# SW6124_A_A_B_C_MCU_LED.net
KiCad netlist of a schematic drawn in Altium Designer
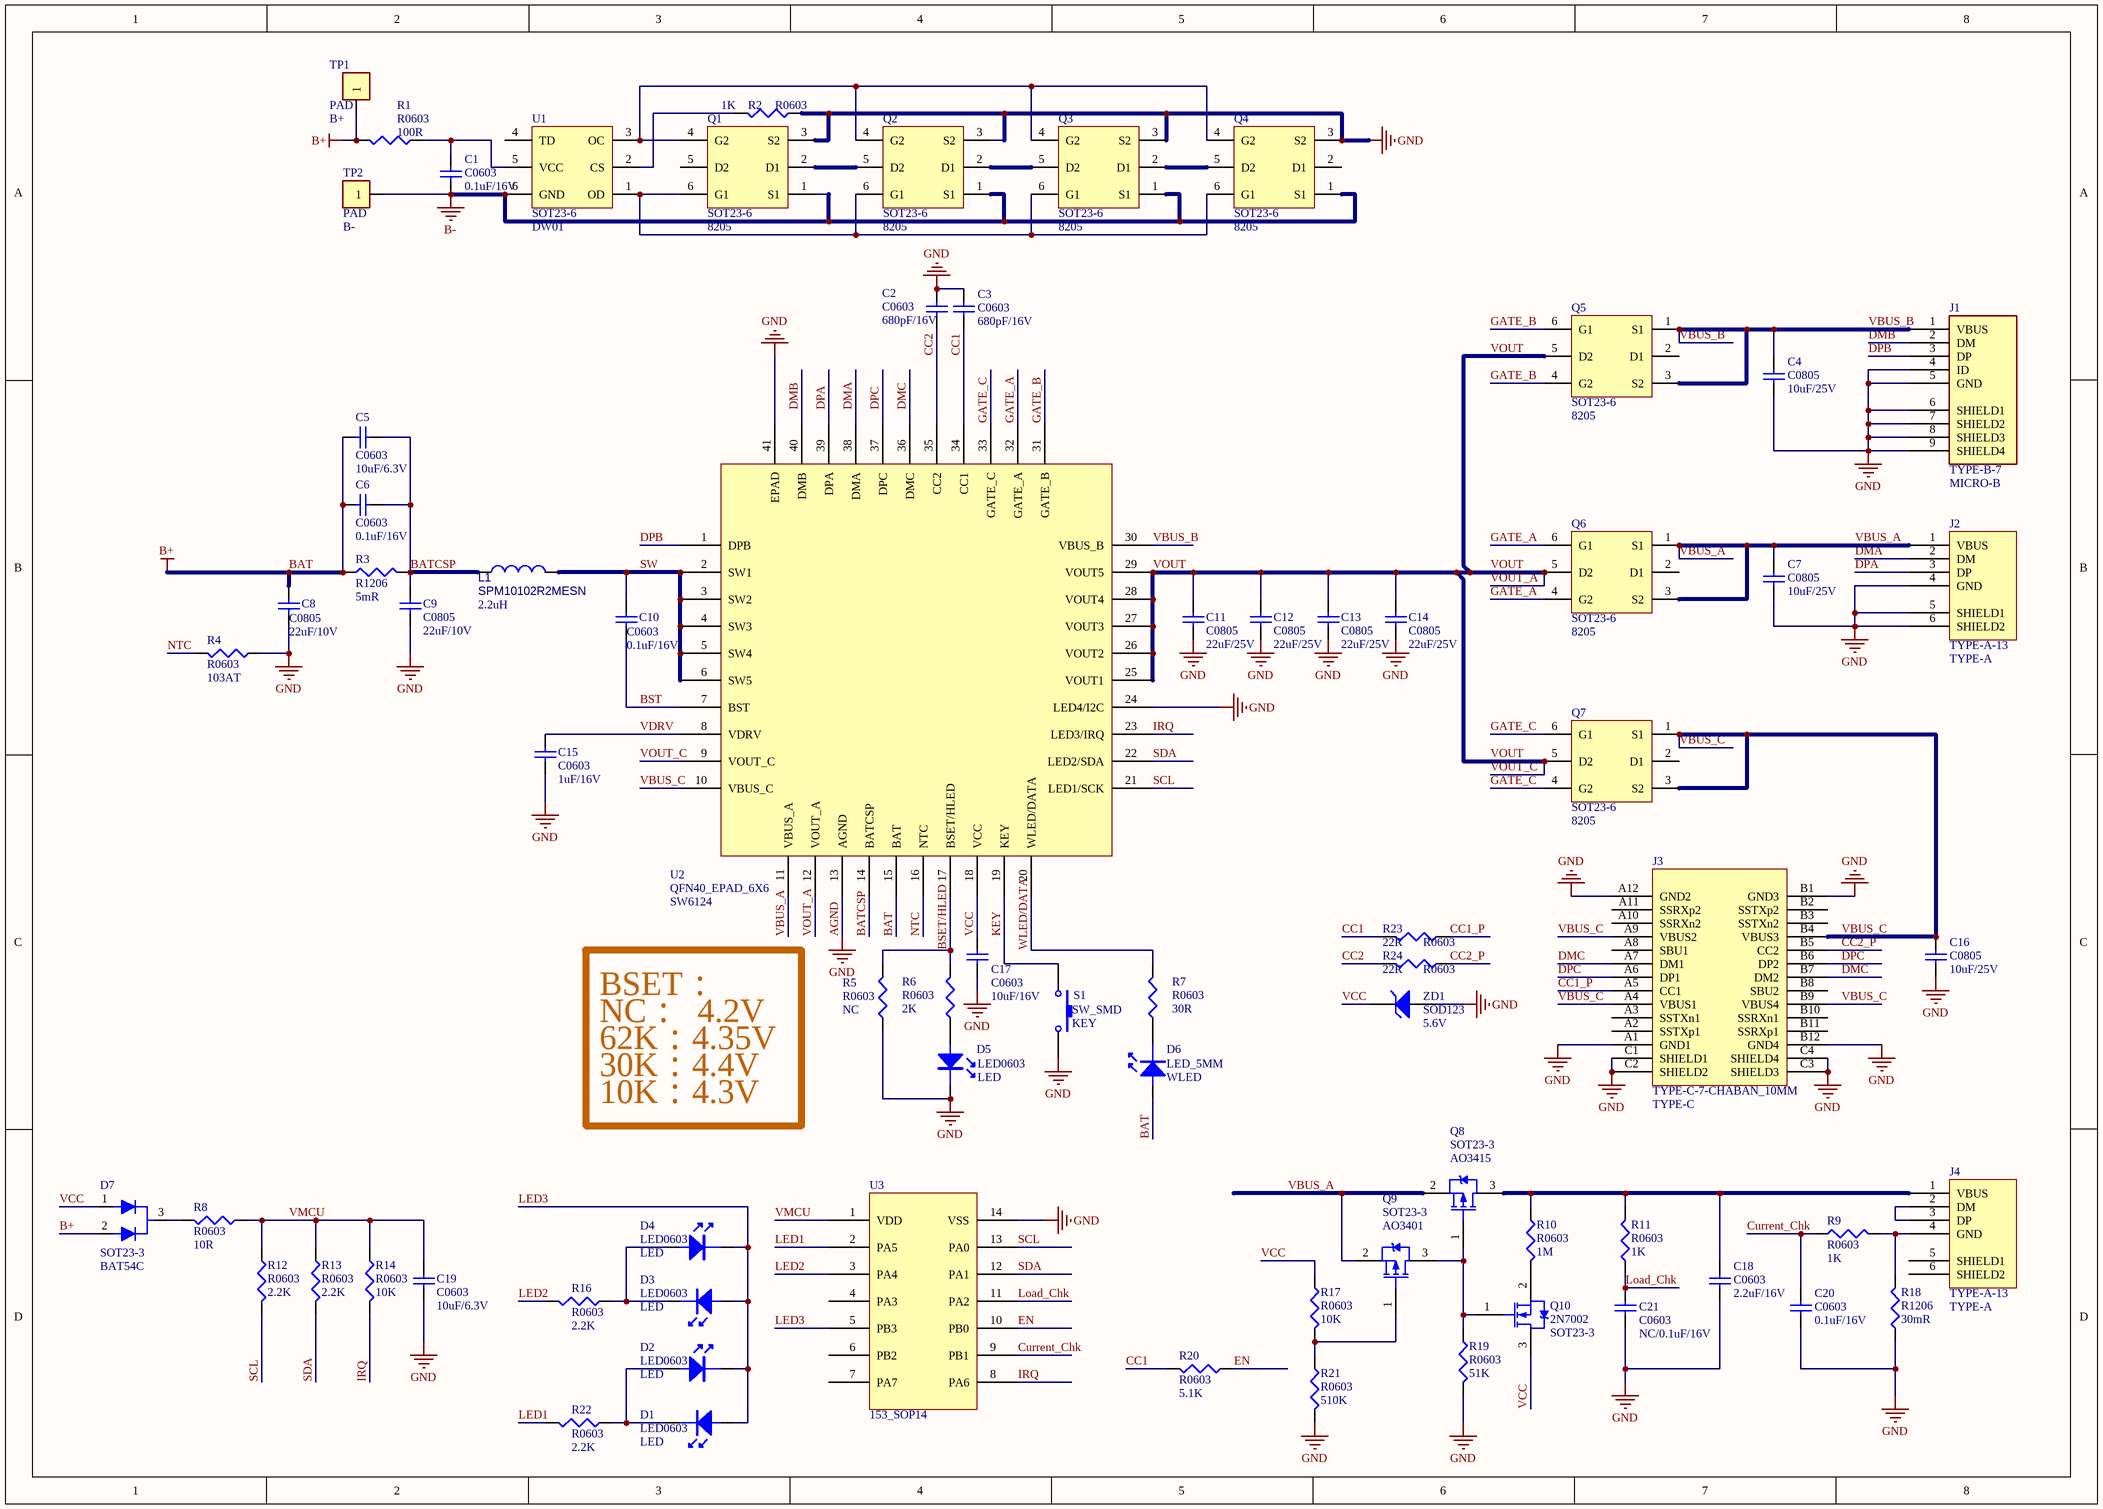
[diagram p0: SW6124+A+A+B+C+MCU+LED.SchDoc]

(export (version "E")
  (design (tool "Eeschema 10.0.6"))
  (components
    (comp (ref "C1")
      (value "C0603")
      (footprint "C0603")
      (description "Capacitor")
      (fields (field (name "ALTIUM_VALUE") "0.1uF/16V") (field (name "PUBLISHER") "Altium Limited"))
      (libsource (lib "*") (part "Cap"))
    )
    (comp (ref "C2")
      (value "C0603")
      (footprint "C0603")
      (description "Capacitor")
      (fields (field (name "ALTIUM_VALUE") "680pF/16V") (field (name "PUBLISHER") "Altium Limited"))
      (libsource (lib "*") (part "CAP0603"))
    )
    (comp (ref "C3")
      (value "C0603")
      (footprint "C0603")
      (description "Capacitor")
      (fields (field (name "ALTIUM_VALUE") "680pF/16V") (field (name "PUBLISHER") "Altium Limited"))
      (libsource (lib "*") (part "CAP0603"))
    )
    (comp (ref "C4")
      (value "C0805")
      (footprint "C0805")
      (description "Capacitor")
      (fields (field (name "ALTIUM_VALUE") "10uF/25V") (field (name "PUBLISHER") "Altium Limited"))
      (libsource (lib "*") (part "CAP0603"))
    )
    (comp (ref "C5")
      (value "C0603")
      (footprint "C0603")
      (description "Capacitor")
      (fields (field (name "ALTIUM_VALUE") "10uF/6.3V") (field (name "PUBLISHER") "Altium Limited"))
      (libsource (lib "*") (part "CAP0603"))
    )
    (comp (ref "C6")
      (value "C0603")
      (footprint "C0603")
      (description "Capacitor")
      (fields (field (name "ALTIUM_VALUE") "0.1uF/16V") (field (name "PUBLISHER") "Altium Limited"))
      (libsource (lib "*") (part "CAP0603"))
    )
    (comp (ref "C7")
      (value "C0805")
      (footprint "C0805")
      (description "Capacitor")
      (fields (field (name "ALTIUM_VALUE") "10uF/25V") (field (name "PUBLISHER") "Altium Limited"))
      (libsource (lib "*") (part "CAP0603"))
    )
    (comp (ref "C8")
      (value "C0805")
      (footprint "C0805")
      (description "Capacitor")
      (fields (field (name "ALTIUM_VALUE") "22uF/10V") (field (name "PUBLISHER") "Altium Limited"))
      (libsource (lib "*") (part "CAP0805"))
    )
    (comp (ref "C9")
      (value "C0805")
      (footprint "C0805")
      (description "Capacitor")
      (fields (field (name "ALTIUM_VALUE") "22uF/10V") (field (name "PUBLISHER") "Altium Limited"))
      (libsource (lib "*") (part "CAP0805"))
    )
    (comp (ref "C10")
      (value "C0603")
      (footprint "C0603")
      (description "Capacitor")
      (fields (field (name "ALTIUM_VALUE") "0.1uF/16V") (field (name "PUBLISHER") "Altium Limited"))
      (libsource (lib "*") (part "CAP0603"))
    )
    (comp (ref "C11")
      (value "C0805")
      (footprint "C0805")
      (description "Capacitor")
      (fields (field (name "ALTIUM_VALUE") "22uF/25V") (field (name "PUBLISHER") "Altium Limited"))
      (libsource (lib "*") (part "CAP0805"))
    )
    (comp (ref "C12")
      (value "C0805")
      (footprint "C0805")
      (description "Capacitor")
      (fields (field (name "ALTIUM_VALUE") "22uF/25V") (field (name "PUBLISHER") "Altium Limited"))
      (libsource (lib "*") (part "CAP0805"))
    )
    (comp (ref "C13")
      (value "C0805")
      (footprint "C0805")
      (description "Capacitor")
      (fields (field (name "ALTIUM_VALUE") "22uF/25V") (field (name "PUBLISHER") "Altium Limited"))
      (libsource (lib "*") (part "CAP0805"))
    )
    (comp (ref "C14")
      (value "C0805")
      (footprint "C0805")
      (description "Capacitor")
      (fields (field (name "ALTIUM_VALUE") "22uF/25V") (field (name "PUBLISHER") "Altium Limited"))
      (libsource (lib "*") (part "CAP0805"))
    )
    (comp (ref "C15")
      (value "C0603")
      (footprint "C0603")
      (description "Capacitor")
      (fields (field (name "ALTIUM_VALUE") "1uF/16V") (field (name "PUBLISHER") "Altium Limited"))
      (libsource (lib "*") (part "CAP0603"))
    )
    (comp (ref "C16")
      (value "C0805")
      (footprint "C0805")
      (description "Capacitor")
      (fields (field (name "ALTIUM_VALUE") "10uF/25V") (field (name "PUBLISHER") "Altium Limited"))
      (libsource (lib "*") (part "CAP0603"))
    )
    (comp (ref "C17")
      (value "C0603")
      (footprint "C0603")
      (description "Capacitor")
      (fields (field (name "ALTIUM_VALUE") "10uF/16V") (field (name "PUBLISHER") "Altium Limited"))
      (libsource (lib "*") (part "CAP0603"))
    )
    (comp (ref "C18")
      (value "C0603")
      (footprint "C0603")
      (description "Capacitor")
      (fields (field (name "ALTIUM_VALUE") "2.2uF/16V") (field (name "PUBLISHER") "Altium Limited"))
      (libsource (lib "*") (part "CAP0603"))
    )
    (comp (ref "C19")
      (value "C0603")
      (footprint "C0603")
      (description "Capacitor")
      (fields (field (name "ALTIUM_VALUE") "10uF/6.3V") (field (name "PUBLISHER") "Altium Limited"))
      (libsource (lib "*") (part "CAP0603"))
    )
    (comp (ref "C20")
      (value "C0603")
      (footprint "C0603")
      (description "Capacitor")
      (fields (field (name "ALTIUM_VALUE") "0.1uF/16V") (field (name "PUBLISHER") "Altium Limited"))
      (libsource (lib "*") (part "CAP0603"))
    )
    (comp (ref "C21")
      (value "C0603")
      (footprint "C0603")
      (description "Capacitor")
      (fields (field (name "ALTIUM_VALUE") "NC/0.1uF/16V") (field (name "PUBLISHER") "Altium Limited"))
      (libsource (lib "*") (part "CAP0603"))
    )
    (comp (ref "D1") (value "LED") (footprint "LED0603") (libsource (lib "*") (part "LED")))
    (comp (ref "D2") (value "LED") (footprint "LED0603") (libsource (lib "*") (part "LED")))
    (comp (ref "D3") (value "LED") (footprint "LED0603") (libsource (lib "*") (part "LED")))
    (comp (ref "D4") (value "LED") (footprint "LED0603") (libsource (lib "*") (part "LED")))
    (comp (ref "D5") (value "LED") (footprint "LED0603") (libsource (lib "*") (part "LED")))
    (comp (ref "D6")
      (value "WLED")
      (footprint "LED_5MM")
      (fields (field (name "FOOTPRINF") "LED_5MM") (field (name "Comment") "LED_5MM"))
      (libsource (lib "*") (part "LED"))
    )
    (comp (ref "D7") (value "BAT54C") (footprint "SOT23-3") (libsource (lib "Schlib1-2012") (part "D3")))
    (comp (ref "J1")
      (value "MICRO-B")
      (footprint "TYPE-B-7")
      (fields (field (name "FOOTPRINTF") "TYPE-B-7") (field (name "Comment") "USB_MICRO_B"))
      (libsource (lib "*") (part "USB_MICRO_B"))
    )
    (comp (ref "J2")
      (value "TYPE-A")
      (footprint "TYPE-A-13")
      (fields (field (name "FOOTPRINF") "TYPE-A-13") (field (name "Comment") "TYPE-A-1"))
      (libsource (lib "*") (part "TYPE-A-1"))
    )
    (comp (ref "J3")
      (value "TYPE-C")
      (footprint "TYPE-C-7-CHABAN_10MM")
      (libsource (lib "*") (part "TYPE-C"))
    )
    (comp (ref "J4")
      (value "TYPE-A")
      (footprint "PIE10-USB")
      (fields (field (name "FOOTPRINF") "TYPE-A-13") (field (name "Comment") "TYPE-A-1"))
      (libsource (lib "*") (part "TYPE-A-1"))
    )
    (comp (ref "L1")
      (value "SPM10102R2MESN")
      (footprint "INDUCTOR_SPM1010")
      (fields (field (name "ALTIUM_VALUE") "2.2uH"))
      (libsource (lib "*") (part "INDUCTOR"))
    )
    (comp (ref "Q1")
      (value "8205")
      (footprint "SOT23-6")
      (fields (field (name "FOOTPRINF") "SOT23-6"))
      (libsource (lib "*") (part "8205B"))
    )
    (comp (ref "Q2")
      (value "8205")
      (footprint "SOT23-6")
      (fields (field (name "FOOTPRINF") "SOT23-6"))
      (libsource (lib "*") (part "8205B"))
    )
    (comp (ref "Q3")
      (value "8205")
      (footprint "SOT23-6")
      (fields (field (name "FOOTPRINF") "SOT23-6"))
      (libsource (lib "*") (part "8205B"))
    )
    (comp (ref "Q4")
      (value "8205")
      (footprint "SOT23-6")
      (fields (field (name "FOOTPRINF") "SOT23-6"))
      (libsource (lib "*") (part "8205B"))
    )
    (comp (ref "Q5")
      (value "8205")
      (footprint "SOT23-6")
      (fields (field (name "FOOTPRINF") "SOT23-6"))
      (libsource (lib "") (part "8205B_1"))
    )
    (comp (ref "Q6")
      (value "8205")
      (footprint "SOT23-6")
      (fields (field (name "FOOTPRINF") "SOT23-6"))
      (libsource (lib "") (part "8205B_1"))
    )
    (comp (ref "Q7")
      (value "8205")
      (footprint "SOT23-6")
      (fields (field (name "FOOTPRINF") "SOT23-6"))
      (libsource (lib "") (part "8205B_1"))
    )
    (comp (ref "Q8")
      (value "AO3415")
      (footprint "SOT23-3")
      (description "P-Channel Power MOSFET")
      (fields (field (name "Comment") "PMOS-2") (field (name "PUBLISHER") "Altium Limited"))
      (libsource (lib "Miscellaneous Devices") (part "PMOS-2"))
    )
    (comp (ref "Q9")
      (value "AO3401")
      (footprint "SOT23-3")
      (description "P-Channel Power MOSFET")
      (fields (field (name "Comment") "PMOS-2") (field (name "PUBLISHER") "Altium Limited"))
      (libsource (lib "Miscellaneous Devices") (part "PMOS-2"))
    )
    (comp (ref "Q10")
      (value "2N7002")
      (footprint "SOT23-3")
      (description "N-Channel Power MOSFET")
      (fields (field (name "Comment") "NMOS-2") (field (name "PUBLISHER") "Altium Limited"))
      (libsource (lib "Miscellaneous Devices") (part "NMOS-2"))
    )
    (comp (ref "R1")
      (value "R0603")
      (footprint "R0603")
      (description "Resistor")
      (fields (field (name "ALTIUM_VALUE") "100R") (field (name "PUBLISHER") "Altium Limited"))
      (libsource (lib "*") (part "Res3"))
    )
    (comp (ref "R2")
      (value "R0603")
      (footprint "R0603")
      (description "Resistor")
      (fields (field (name "ALTIUM_VALUE") "1K") (field (name "PUBLISHER") "Altium Limited"))
      (libsource (lib "*") (part "Res3"))
    )
    (comp (ref "R3")
      (value "R1206")
      (footprint "R1206")
      (description "Resistor")
      (fields (field (name "ALTIUM_VALUE") "5mR") (field (name "PUBLISHER") "Altium Limited"))
      (libsource (lib "*") (part "RES"))
    )
    (comp (ref "R4")
      (value "R0603")
      (footprint "R0603")
      (description "Resistor")
      (fields (field (name "ALTIUM_VALUE") "103AT") (field (name "PUBLISHER") "Altium Limited"))
      (libsource (lib "*") (part "RES"))
    )
    (comp (ref "R5")
      (value "R0603")
      (footprint "R0603")
      (description "Resistor")
      (fields (field (name "ALTIUM_VALUE") "NC") (field (name "PUBLISHER") "Altium Limited"))
      (libsource (lib "*") (part "RES"))
    )
    (comp (ref "R6")
      (value "R0603")
      (footprint "R0603")
      (description "Resistor")
      (fields (field (name "ALTIUM_VALUE") "2K") (field (name "PUBLISHER") "Altium Limited"))
      (libsource (lib "*") (part "RES"))
    )
    (comp (ref "R7")
      (value "R0603")
      (footprint "R0603")
      (description "Resistor")
      (fields (field (name "ALTIUM_VALUE") "30R") (field (name "PUBLISHER") "Altium Limited"))
      (libsource (lib "*") (part "RES"))
    )
    (comp (ref "R8")
      (value "R0603")
      (footprint "R0603")
      (description "Resistor")
      (fields (field (name "ALTIUM_VALUE") "10R") (field (name "PUBLISHER") "Altium Limited"))
      (libsource (lib "*") (part "RES"))
    )
    (comp (ref "R9")
      (value "R0603")
      (footprint "R0603")
      (description "Resistor")
      (fields (field (name "ALTIUM_VALUE") "1K") (field (name "PUBLISHER") "Altium Limited"))
      (libsource (lib "*") (part "RES"))
    )
    (comp (ref "R10")
      (value "R0603")
      (footprint "R0603")
      (description "Resistor")
      (fields (field (name "ALTIUM_VALUE") "1M") (field (name "PUBLISHER") "Altium Limited"))
      (libsource (lib "*") (part "RES"))
    )
    (comp (ref "R11")
      (value "R0603")
      (footprint "R0603")
      (description "Resistor")
      (fields (field (name "ALTIUM_VALUE") "1K") (field (name "PUBLISHER") "Altium Limited"))
      (libsource (lib "*") (part "RES"))
    )
    (comp (ref "R12")
      (value "R0603")
      (footprint "R0603")
      (description "Resistor")
      (fields (field (name "ALTIUM_VALUE") "2.2K") (field (name "PUBLISHER") "Altium Limited"))
      (libsource (lib "*") (part "RES"))
    )
    (comp (ref "R13")
      (value "R0603")
      (footprint "R0603")
      (description "Resistor")
      (fields (field (name "ALTIUM_VALUE") "2.2K") (field (name "PUBLISHER") "Altium Limited"))
      (libsource (lib "*") (part "RES"))
    )
    (comp (ref "R14")
      (value "R0603")
      (footprint "R0603")
      (description "Resistor")
      (fields (field (name "ALTIUM_VALUE") "10K") (field (name "PUBLISHER") "Altium Limited"))
      (libsource (lib "*") (part "RES"))
    )
    (comp (ref "R16")
      (value "R0603")
      (footprint "R0603")
      (description "Resistor")
      (fields (field (name "ALTIUM_VALUE") "2.2K") (field (name "PUBLISHER") "Altium Limited"))
      (libsource (lib "*") (part "RES"))
    )
    (comp (ref "R17")
      (value "R0603")
      (footprint "R0603")
      (description "Resistor")
      (fields (field (name "ALTIUM_VALUE") "10K") (field (name "PUBLISHER") "Altium Limited"))
      (libsource (lib "*") (part "RES"))
    )
    (comp (ref "R18")
      (value "R1206")
      (footprint "C-1206A")
      (description "Resistor")
      (fields (field (name "ALTIUM_VALUE") "30mR") (field (name "PUBLISHER") "Altium Limited"))
      (libsource (lib "*") (part "RES"))
    )
    (comp (ref "R19")
      (value "R0603")
      (footprint "R0603")
      (description "Resistor")
      (fields (field (name "ALTIUM_VALUE") "51K") (field (name "PUBLISHER") "Altium Limited"))
      (libsource (lib "*") (part "RES"))
    )
    (comp (ref "R20")
      (value "R0603")
      (footprint "R0603")
      (description "Resistor")
      (fields (field (name "ALTIUM_VALUE") "5.1K") (field (name "PUBLISHER") "Altium Limited"))
      (libsource (lib "*") (part "RES"))
    )
    (comp (ref "R21")
      (value "R0603")
      (footprint "R0603")
      (description "Resistor")
      (fields (field (name "ALTIUM_VALUE") "510K") (field (name "PUBLISHER") "Altium Limited"))
      (libsource (lib "*") (part "RES"))
    )
    (comp (ref "R22")
      (value "R0603")
      (footprint "R0603")
      (description "Resistor")
      (fields (field (name "ALTIUM_VALUE") "2.2K") (field (name "PUBLISHER") "Altium Limited"))
      (libsource (lib "*") (part "RES"))
    )
    (comp (ref "R23")
      (value "R0603")
      (footprint "R0603")
      (description "Resistor")
      (fields (field (name "ALTIUM_VALUE") "22R") (field (name "PUBLISHER") "Altium Limited"))
      (libsource (lib "*") (part "RES"))
    )
    (comp (ref "R24")
      (value "R0603")
      (footprint "R0603")
      (description "Resistor")
      (fields (field (name "ALTIUM_VALUE") "22R") (field (name "PUBLISHER") "Altium Limited"))
      (libsource (lib "*") (part "RES"))
    )
    (comp (ref "S1")
      (value "KEY")
      (footprint "SW_SMD")
      (fields (field (name "FOOTPRINF") "SW_SMD"))
      (libsource (lib "*") (part "SW K"))
    )
    (comp (ref "TP1") (value "B+") (footprint "PAD") (libsource (lib "") (part "Test Point_1")))
    (comp (ref "TP2") (value "B-") (footprint "PAD") (libsource (lib "*") (part "Test Point")))
    (comp (ref "U1")
      (value "DW01")
      (footprint "SOT23-6")
      (fields (field (name "FOOTPRINF") "SOT23-6"))
      (libsource (lib "*") (part "DW01"))
    )
    (comp (ref "U2")
      (value "SW6124")
      (footprint "QFN40_EPAD_6X6")
      (libsource (lib "TEST") (part "SW6106_AFC"))
    )
    (comp (ref "U3") (value "153_SOP14") (libsource (lib "TEST") (part "153_SOP14")))
    (comp (ref "ZD1")
      (value "SOD123")
      (footprint "SOD-123")
      (description "Zener Diode")
      (fields (field (name "ALTIUM_UNNAMED_1") "5.6V"))
      (libsource (lib "Miscellaneous Devices") (part "D Zener"))
    )
  )
  (nets
    (net (code "1") (name "/BATCSP") (class "Default")
      (node (ref "C5") (pin "2") (pinfunction "2_2") (pintype "passive"))
      (node (ref "C6") (pin "2") (pinfunction "2_2") (pintype "passive"))
      (node (ref "C9") (pin "2") (pinfunction "2_2") (pintype "passive"))
      (node (ref "L1") (pin "1") (pinfunction "1_1") (pintype "passive"))
      (node (ref "R3") (pin "2") (pinfunction "2_2") (pintype "passive"))
      (node (ref "U2") (pin "14") (pinfunction "BATCSP_14") (pintype "passive"))
    )
    (net (code "2") (name "/BSET{slash}HLED") (class "Default")
      (node (ref "R5") (pin "2") (pinfunction "2_2") (pintype "passive"))
      (node (ref "R6") (pin "2") (pinfunction "2_2") (pintype "passive"))
      (node (ref "U2") (pin "17") (pinfunction "BSET/HLED_17") (pintype "passive"))
    )
    (net (code "3") (name "/BST") (class "Default")
      (node (ref "C10") (pin "1") (pinfunction "1_1") (pintype "passive"))
      (node (ref "U2") (pin "7") (pinfunction "BST_7") (pintype "passive"))
    )
    (net (code "4") (name "/CC1") (class "Default")
      (node (ref "C3") (pin "1") (pinfunction "1_1") (pintype "passive"))
      (node (ref "R20") (pin "2") (pinfunction "2_2") (pintype "passive"))
      (node (ref "R23") (pin "2") (pinfunction "2_2") (pintype "passive"))
      (node (ref "U2") (pin "34") (pinfunction "CC1_34") (pintype "passive"))
    )
    (net (code "5") (name "/CC1_P") (class "Default")
      (node (ref "J3") (pin "A5") (pinfunction "CC1_A5") (pintype "passive"))
      (node (ref "R23") (pin "1") (pinfunction "1_1") (pintype "passive"))
    )
    (net (code "6") (name "/CC2") (class "Default")
      (node (ref "C2") (pin "1") (pinfunction "1_1") (pintype "passive"))
      (node (ref "R24") (pin "2") (pinfunction "2_2") (pintype "passive"))
      (node (ref "U2") (pin "35") (pinfunction "CC2_35") (pintype "passive"))
    )
    (net (code "7") (name "/CC2_P") (class "Default")
      (node (ref "J3") (pin "B5") (pinfunction "CC2_B5") (pintype "passive"))
      (node (ref "R24") (pin "1") (pinfunction "1_1") (pintype "passive"))
    )
    (net (code "8") (name "/Current_Chk") (class "Default")
      (node (ref "C20") (pin "2") (pinfunction "2_2") (pintype "passive"))
      (node (ref "R9") (pin "1") (pinfunction "1_1") (pintype "passive"))
      (node (ref "U3") (pin "9") (pinfunction "PB1_9") (pintype "passive"))
    )
    (net (code "9") (name "/DMA") (class "Default")
      (node (ref "J2") (pin "2") (pinfunction "DM_2") (pintype "passive"))
      (node (ref "U2") (pin "38") (pinfunction "DMA_38") (pintype "passive"))
    )
    (net (code "10") (name "/DMB") (class "Default")
      (node (ref "J1") (pin "2") (pinfunction "DM_2") (pintype "passive"))
      (node (ref "U2") (pin "40") (pinfunction "DMB_40") (pintype "passive"))
    )
    (net (code "11") (name "/DMC") (class "Default")
      (node (ref "J3") (pin "A7") (pinfunction "DM1_A7") (pintype "passive"))
      (node (ref "J3") (pin "B7") (pinfunction "DM2_B7") (pintype "passive"))
      (node (ref "U2") (pin "36") (pinfunction "DMC_36") (pintype "passive"))
    )
    (net (code "12") (name "/DPA") (class "Default")
      (node (ref "J2") (pin "3") (pinfunction "DP_3") (pintype "passive"))
      (node (ref "U2") (pin "39") (pinfunction "DPA_39") (pintype "passive"))
    )
    (net (code "13") (name "/DPB") (class "Default")
      (node (ref "J1") (pin "3") (pinfunction "DP_3") (pintype "passive"))
      (node (ref "U2") (pin "1") (pinfunction "DPB_1") (pintype "passive"))
    )
    (net (code "14") (name "/DPC") (class "Default")
      (node (ref "J3") (pin "A6") (pinfunction "DP1_A6") (pintype "passive"))
      (node (ref "J3") (pin "B6") (pinfunction "DP2_B6") (pintype "passive"))
      (node (ref "U2") (pin "37") (pinfunction "DPC_37") (pintype "passive"))
    )
    (net (code "15") (name "/EN") (class "Default")
      (node (ref "R20") (pin "1") (pinfunction "1_1") (pintype "passive"))
      (node (ref "U3") (pin "10") (pinfunction "PB0_10") (pintype "passive"))
    )
    (net (code "16") (name "/GATE_A") (class "Default")
      (node (ref "Q6") (pin "4") (pinfunction "G2_4") (pintype "passive"))
      (node (ref "Q6") (pin "6") (pinfunction "G1_6") (pintype "passive"))
      (node (ref "U2") (pin "32") (pinfunction "GATE_A_32") (pintype "passive"))
    )
    (net (code "17") (name "/GATE_B") (class "Default")
      (node (ref "Q5") (pin "4") (pinfunction "G2_4") (pintype "passive"))
      (node (ref "Q5") (pin "6") (pinfunction "G1_6") (pintype "passive"))
      (node (ref "U2") (pin "31") (pinfunction "GATE_B_31") (pintype "passive"))
    )
    (net (code "18") (name "/GATE_C") (class "Default")
      (node (ref "Q7") (pin "4") (pinfunction "G2_4") (pintype "passive"))
      (node (ref "Q7") (pin "6") (pinfunction "G1_6") (pintype "passive"))
      (node (ref "U2") (pin "33") (pinfunction "GATE_C_33") (pintype "passive"))
    )
    (net (code "19") (name "/IRQ") (class "Default")
      (node (ref "R14") (pin "2") (pinfunction "2_2") (pintype "passive"))
      (node (ref "U2") (pin "23") (pinfunction "LED3/IRQ_23") (pintype "passive"))
      (node (ref "U3") (pin "8") (pinfunction "PA6_8") (pintype "passive"))
    )
    (net (code "20") (name "/KEY") (class "Default")
      (node (ref "S1") (pin "1") (pinfunction "1_1") (pintype "passive"))
      (node (ref "U2") (pin "19") (pinfunction "KEY_19") (pintype "passive"))
    )
    (net (code "21") (name "/LED1") (class "Default")
      (node (ref "R22") (pin "2") (pinfunction "2_2") (pintype "passive"))
      (node (ref "U3") (pin "2") (pinfunction "PA5_2") (pintype "passive"))
    )
    (net (code "22") (name "/LED2") (class "Default")
      (node (ref "R16") (pin "2") (pinfunction "2_2") (pintype "passive"))
      (node (ref "U3") (pin "3") (pinfunction "PA4_3") (pintype "passive"))
    )
    (net (code "23") (name "/LED3") (class "Default")
      (node (ref "D1") (pin "1") (pinfunction "A_1") (pintype "passive"))
      (node (ref "D2") (pin "2") (pinfunction "K_2") (pintype "passive"))
      (node (ref "D3") (pin "1") (pinfunction "A_1") (pintype "passive"))
      (node (ref "D4") (pin "2") (pinfunction "K_2") (pintype "passive"))
      (node (ref "U3") (pin "5") (pinfunction "PB3_5") (pintype "passive"))
    )
    (net (code "24") (name "/Load_Chk") (class "Default")
      (node (ref "C21") (pin "2") (pinfunction "2_2") (pintype "passive"))
      (node (ref "R11") (pin "1") (pinfunction "1_1") (pintype "passive"))
      (node (ref "U3") (pin "11") (pinfunction "PA2_11") (pintype "passive"))
    )
    (net (code "25") (name "/NTC") (class "Default")
      (node (ref "R4") (pin "2") (pinfunction "2_2") (pintype "passive"))
      (node (ref "U2") (pin "16") (pinfunction "NTC_16") (pintype "passive"))
    )
    (net (code "26") (name "/SCL") (class "Default")
      (node (ref "R12") (pin "2") (pinfunction "2_2") (pintype "passive"))
      (node (ref "U2") (pin "21") (pinfunction "LED1/SCK_21") (pintype "passive"))
      (node (ref "U3") (pin "13") (pinfunction "PA0_13") (pintype "passive"))
    )
    (net (code "27") (name "/SDA") (class "Default")
      (node (ref "R13") (pin "2") (pinfunction "2_2") (pintype "passive"))
      (node (ref "U2") (pin "22") (pinfunction "LED2/SDA_22") (pintype "passive"))
      (node (ref "U3") (pin "12") (pinfunction "PA1_12") (pintype "passive"))
    )
    (net (code "28") (name "/SW") (class "Default")
      (node (ref "C10") (pin "2") (pinfunction "2_2") (pintype "passive"))
      (node (ref "L1") (pin "2") (pinfunction "2_2") (pintype "passive"))
      (node (ref "U2") (pin "2") (pinfunction "SW1_2") (pintype "passive"))
      (node (ref "U2") (pin "3") (pinfunction "SW2_3") (pintype "passive"))
      (node (ref "U2") (pin "4") (pinfunction "SW3_4") (pintype "passive"))
      (node (ref "U2") (pin "5") (pinfunction "SW4_5") (pintype "passive"))
      (node (ref "U2") (pin "6") (pinfunction "SW5_6") (pintype "passive"))
    )
    (net (code "29") (name "/VBUS_A") (class "Default")
      (node (ref "C7") (pin "2") (pinfunction "2_2") (pintype "passive"))
      (node (ref "J2") (pin "1") (pinfunction "VBUS_1") (pintype "passive"))
      (node (ref "Q6") (pin "1") (pinfunction "S1_1") (pintype "passive"))
      (node (ref "Q6") (pin "3") (pinfunction "S2_3") (pintype "passive"))
      (node (ref "Q8") (pin "2") (pinfunction "S_2") (pintype "passive"))
      (node (ref "Q9") (pin "2") (pinfunction "S_2") (pintype "passive"))
      (node (ref "U2") (pin "11") (pinfunction "VBUS_A_11") (pintype "passive"))
    )
    (net (code "30") (name "/VBUS_B") (class "Default")
      (node (ref "C4") (pin "2") (pinfunction "2_2") (pintype "passive"))
      (node (ref "J1") (pin "1") (pinfunction "VBUS_1") (pintype "passive"))
      (node (ref "Q5") (pin "1") (pinfunction "S1_1") (pintype "passive"))
      (node (ref "Q5") (pin "3") (pinfunction "S2_3") (pintype "passive"))
      (node (ref "U2") (pin "30") (pinfunction "VBUS_B_30") (pintype "passive"))
    )
    (net (code "31") (name "/VBUS_C") (class "Default")
      (node (ref "C16") (pin "2") (pinfunction "2_2") (pintype "passive"))
      (node (ref "J3") (pin "A4") (pinfunction "VBUS1_A4") (pintype "passive"))
      (node (ref "J3") (pin "A9") (pinfunction "VBUS2_A9") (pintype "passive"))
      (node (ref "J3") (pin "B4") (pinfunction "VBUS3_B4") (pintype "passive"))
      (node (ref "J3") (pin "B9") (pinfunction "VBUS4_B9") (pintype "passive"))
      (node (ref "Q7") (pin "1") (pinfunction "S1_1") (pintype "passive"))
      (node (ref "Q7") (pin "3") (pinfunction "S2_3") (pintype "passive"))
      (node (ref "U2") (pin "10") (pinfunction "VBUS_C_10") (pintype "passive"))
    )
    (net (code "32") (name "/VCC") (class "Default")
      (node (ref "C17") (pin "2") (pinfunction "2_2") (pintype "passive"))
      (node (ref "D7") (pin "1") (pintype "passive"))
      (node (ref "Q10") (pin "3") (pinfunction "D_3") (pintype "passive"))
      (node (ref "R17") (pin "1") (pinfunction "1_1") (pintype "passive"))
      (node (ref "U2") (pin "18") (pinfunction "VCC_18") (pintype "passive"))
      (node (ref "ZD1") (pin "2") (pinfunction "K_2") (pintype "passive"))
    )
    (net (code "33") (name "/VDRV") (class "Default")
      (node (ref "C15") (pin "2") (pinfunction "2_2") (pintype "passive"))
      (node (ref "U2") (pin "8") (pinfunction "VDRV_8") (pintype "passive"))
    )
    (net (code "34") (name "/VMCU") (class "Default")
      (node (ref "C19") (pin "1") (pinfunction "1_1") (pintype "passive"))
      (node (ref "R12") (pin "1") (pinfunction "1_1") (pintype "passive"))
      (node (ref "R13") (pin "1") (pinfunction "1_1") (pintype "passive"))
      (node (ref "R14") (pin "1") (pinfunction "1_1") (pintype "passive"))
      (node (ref "R8") (pin "1") (pinfunction "1_1") (pintype "passive"))
      (node (ref "U3") (pin "1") (pinfunction "VDD_1") (pintype "passive"))
    )
    (net (code "35") (name "/VOUT") (class "Default")
      (node (ref "C11") (pin "2") (pinfunction "2_2") (pintype "passive"))
      (node (ref "C12") (pin "2") (pinfunction "2_2") (pintype "passive"))
      (node (ref "C13") (pin "2") (pinfunction "2_2") (pintype "passive"))
      (node (ref "C14") (pin "2") (pinfunction "2_2") (pintype "passive"))
      (node (ref "Q5") (pin "5") (pinfunction "D2_5") (pintype "passive"))
      (node (ref "Q6") (pin "5") (pinfunction "D2_5") (pintype "passive"))
      (node (ref "Q7") (pin "5") (pinfunction "D2_5") (pintype "passive"))
      (node (ref "U2") (pin "12") (pinfunction "VOUT_A_12") (pintype "passive"))
      (node (ref "U2") (pin "25") (pinfunction "VOUT1_25") (pintype "passive"))
      (node (ref "U2") (pin "26") (pinfunction "VOUT2_26") (pintype "passive"))
      (node (ref "U2") (pin "27") (pinfunction "VOUT3_27") (pintype "passive"))
      (node (ref "U2") (pin "28") (pinfunction "VOUT4_28") (pintype "passive"))
      (node (ref "U2") (pin "29") (pinfunction "VOUT5_29") (pintype "passive"))
      (node (ref "U2") (pin "9") (pinfunction "VOUT_C_9") (pintype "passive"))
    )
    (net (code "36") (name "/WLED{slash}DATA") (class "Default")
      (node (ref "R7") (pin "2") (pinfunction "2_2") (pintype "passive"))
      (node (ref "U2") (pin "20") (pinfunction "WLED/DATA_20") (pintype "passive"))
    )
    (net (code "37") (name "B+") (class "Default")
      (node (ref "C5") (pin "1") (pinfunction "1_1") (pintype "passive"))
      (node (ref "C6") (pin "1") (pinfunction "1_1") (pintype "passive"))
      (node (ref "C8") (pin "2") (pinfunction "2_2") (pintype "passive"))
      (node (ref "D6") (pin "1") (pinfunction "A_1") (pintype "passive"))
      (node (ref "D7") (pin "2") (pintype "passive"))
      (node (ref "R1") (pin "2") (pinfunction "2_2") (pintype "passive"))
      (node (ref "R3") (pin "1") (pinfunction "1_1") (pintype "passive"))
      (node (ref "TP1") (pin "1") (pinfunction "1_1") (pintype "passive"))
      (node (ref "U2") (pin "15") (pinfunction "BAT_15") (pintype "passive"))
    )
    (net (code "38") (name "B-") (class "Default")
      (node (ref "C1") (pin "1") (pinfunction "1_1") (pintype "passive"))
      (node (ref "Q1") (pin "1") (pinfunction "S1_1") (pintype "passive"))
      (node (ref "Q2") (pin "1") (pinfunction "S1_1") (pintype "passive"))
      (node (ref "Q3") (pin "1") (pinfunction "S1_1") (pintype "passive"))
      (node (ref "Q4") (pin "1") (pinfunction "S1_1") (pintype "passive"))
      (node (ref "TP2") (pin "1") (pinfunction "1_1") (pintype "passive"))
      (node (ref "U1") (pin "6") (pinfunction "GND_6") (pintype "passive"))
    )
    (net (code "39") (name "GND") (class "Default")
      (node (ref "C11") (pin "1") (pinfunction "1_1") (pintype "passive"))
      (node (ref "C12") (pin "1") (pinfunction "1_1") (pintype "passive"))
      (node (ref "C13") (pin "1") (pinfunction "1_1") (pintype "passive"))
      (node (ref "C14") (pin "1") (pinfunction "1_1") (pintype "passive"))
      (node (ref "C15") (pin "1") (pinfunction "1_1") (pintype "passive"))
      (node (ref "C16") (pin "1") (pinfunction "1_1") (pintype "passive"))
      (node (ref "C17") (pin "1") (pinfunction "1_1") (pintype "passive"))
      (node (ref "C18") (pin "1") (pinfunction "1_1") (pintype "passive"))
      (node (ref "C19") (pin "2") (pinfunction "2_2") (pintype "passive"))
      (node (ref "C2") (pin "2") (pinfunction "2_2") (pintype "passive"))
      (node (ref "C20") (pin "1") (pinfunction "1_1") (pintype "passive"))
      (node (ref "C21") (pin "1") (pinfunction "1_1") (pintype "passive"))
      (node (ref "C3") (pin "2") (pinfunction "2_2") (pintype "passive"))
      (node (ref "C4") (pin "1") (pinfunction "1_1") (pintype "passive"))
      (node (ref "C7") (pin "1") (pinfunction "1_1") (pintype "passive"))
      (node (ref "C8") (pin "1") (pinfunction "1_1") (pintype "passive"))
      (node (ref "C9") (pin "1") (pinfunction "1_1") (pintype "passive"))
      (node (ref "D5") (pin "2") (pinfunction "K_2") (pintype "passive"))
      (node (ref "J1") (pin "4") (pinfunction "ID_4") (pintype "passive"))
      (node (ref "J1") (pin "5") (pinfunction "GND_5") (pintype "passive"))
      (node (ref "J1") (pin "6") (pinfunction "SHIELD1_6") (pintype "passive"))
      (node (ref "J1") (pin "7") (pinfunction "SHIELD2_7") (pintype "passive"))
      (node (ref "J1") (pin "8") (pinfunction "SHIELD3_8") (pintype "passive"))
      (node (ref "J1") (pin "9") (pinfunction "SHIELD4_9") (pintype "passive"))
      (node (ref "J2") (pin "4") (pinfunction "GND_4") (pintype "passive"))
      (node (ref "J2") (pin "5") (pinfunction "SHIELD1_5") (pintype "passive"))
      (node (ref "J2") (pin "6") (pinfunction "SHIELD2_6") (pintype "passive"))
      (node (ref "J3") (pin "A1") (pinfunction "GND1_A1") (pintype "passive"))
      (node (ref "J3") (pin "A12") (pinfunction "GND2_A12") (pintype "passive"))
      (node (ref "J3") (pin "B1") (pinfunction "GND3_B1") (pintype "passive"))
      (node (ref "J3") (pin "B12") (pinfunction "GND4_B12") (pintype "passive"))
      (node (ref "J3") (pin "C1") (pinfunction "SHIELD1_C1") (pintype "passive"))
      (node (ref "J3") (pin "C2") (pinfunction "SHIELD2_C2") (pintype "passive"))
      (node (ref "J3") (pin "C3") (pinfunction "SHIELD3_C3") (pintype "passive"))
      (node (ref "J3") (pin "C4") (pinfunction "SHIELD4_C4") (pintype "passive"))
      (node (ref "Q1") (pin "3") (pinfunction "S2_3") (pintype "passive"))
      (node (ref "Q2") (pin "3") (pinfunction "S2_3") (pintype "passive"))
      (node (ref "Q3") (pin "3") (pinfunction "S2_3") (pintype "passive"))
      (node (ref "Q4") (pin "3") (pinfunction "S2_3") (pintype "passive"))
      (node (ref "R18") (pin "1") (pinfunction "1_1") (pintype "passive"))
      (node (ref "R19") (pin "2") (pinfunction "2_2") (pintype "passive"))
      (node (ref "R2") (pin "1") (pinfunction "1_1") (pintype "passive"))
      (node (ref "R21") (pin "2") (pinfunction "2_2") (pintype "passive"))
      (node (ref "R4") (pin "1") (pinfunction "1_1") (pintype "passive"))
      (node (ref "R5") (pin "1") (pinfunction "1_1") (pintype "passive"))
      (node (ref "S1") (pin "2") (pinfunction "2_2") (pintype "passive"))
      (node (ref "U2") (pin "13") (pinfunction "AGND_13") (pintype "passive"))
      (node (ref "U2") (pin "24") (pinfunction "LED4/I2C_24") (pintype "passive"))
      (node (ref "U2") (pin "41") (pinfunction "EPAD_41") (pintype "passive"))
      (node (ref "U3") (pin "14") (pinfunction "VSS_14") (pintype "passive"))
      (node (ref "ZD1") (pin "1") (pinfunction "A_1") (pintype "passive"))
    )
    (net (code "40") (name "Net-(D1-K)") (class "Default")
      (node (ref "D1") (pin "2") (pinfunction "K_2") (pintype "passive"))
      (node (ref "D2") (pin "1") (pinfunction "A_1") (pintype "passive"))
      (node (ref "R22") (pin "1") (pinfunction "1_1") (pintype "passive"))
    )
    (net (code "41") (name "Net-(D3-K)") (class "Default")
      (node (ref "D3") (pin "2") (pinfunction "K_2") (pintype "passive"))
      (node (ref "D4") (pin "1") (pinfunction "A_1") (pintype "passive"))
      (node (ref "R16") (pin "1") (pinfunction "1_1") (pintype "passive"))
    )
    (net (code "42") (name "Net-(D5-A)") (class "Default")
      (node (ref "D5") (pin "1") (pinfunction "A_1") (pintype "passive"))
      (node (ref "R6") (pin "1") (pinfunction "1_1") (pintype "passive"))
    )
    (net (code "43") (name "Net-(D6-K)") (class "Default")
      (node (ref "D6") (pin "2") (pinfunction "K_2") (pintype "passive"))
      (node (ref "R7") (pin "1") (pinfunction "1_1") (pintype "passive"))
    )
    (net (code "44") (name "Net-(D7-Pad3)") (class "Default")
      (node (ref "D7") (pin "3") (pintype "passive"))
      (node (ref "R8") (pin "2") (pinfunction "2_2") (pintype "passive"))
    )
    (net (code "45") (name "Net-(J4-DM)") (class "Default")
      (node (ref "J4") (pin "2") (pinfunction "DM_2") (pintype "passive"))
      (node (ref "J4") (pin "3") (pinfunction "DP_3") (pintype "passive"))
    )
    (net (code "46") (name "Net-(J4-GND)") (class "Default")
      (node (ref "J4") (pin "4") (pinfunction "GND_4") (pintype "passive"))
      (node (ref "R18") (pin "2") (pinfunction "2_2") (pintype "passive"))
      (node (ref "R9") (pin "2") (pinfunction "2_2") (pintype "passive"))
    )
    (net (code "47") (name "Net-(J4-VBUS)") (class "Default")
      (node (ref "C18") (pin "2") (pinfunction "2_2") (pintype "passive"))
      (node (ref "J4") (pin "1") (pinfunction "VBUS_1") (pintype "passive"))
      (node (ref "Q8") (pin "3") (pinfunction "D_3") (pintype "passive"))
      (node (ref "R10") (pin "1") (pinfunction "1_1") (pintype "passive"))
      (node (ref "R11") (pin "2") (pinfunction "2_2") (pintype "passive"))
    )
    (net (code "48") (name "Net-(Q1-D1)") (class "Default")
      (node (ref "Q1") (pin "2") (pinfunction "D1_2") (pintype "passive"))
      (node (ref "Q2") (pin "5") (pinfunction "D2_5") (pintype "passive"))
    )
    (net (code "49") (name "Net-(Q1-G1)") (class "Default")
      (node (ref "Q1") (pin "6") (pinfunction "G1_6") (pintype "passive"))
      (node (ref "Q2") (pin "6") (pinfunction "G1_6") (pintype "passive"))
      (node (ref "Q3") (pin "6") (pinfunction "G1_6") (pintype "passive"))
      (node (ref "Q4") (pin "6") (pinfunction "G1_6") (pintype "passive"))
      (node (ref "U1") (pin "1") (pinfunction "OD_1") (pintype "passive"))
    )
    (net (code "50") (name "Net-(Q1-G2)") (class "Default")
      (node (ref "Q1") (pin "4") (pinfunction "G2_4") (pintype "passive"))
      (node (ref "Q2") (pin "4") (pinfunction "G2_4") (pintype "passive"))
      (node (ref "Q3") (pin "4") (pinfunction "G2_4") (pintype "passive"))
      (node (ref "Q4") (pin "4") (pinfunction "G2_4") (pintype "passive"))
      (node (ref "U1") (pin "3") (pinfunction "OC_3") (pintype "passive"))
    )
    (net (code "51") (name "Net-(Q2-D1)") (class "Default")
      (node (ref "Q2") (pin "2") (pinfunction "D1_2") (pintype "passive"))
      (node (ref "Q3") (pin "5") (pinfunction "D2_5") (pintype "passive"))
    )
    (net (code "52") (name "Net-(Q3-D1)") (class "Default")
      (node (ref "Q3") (pin "2") (pinfunction "D1_2") (pintype "passive"))
      (node (ref "Q4") (pin "5") (pinfunction "D2_5") (pintype "passive"))
    )
    (net (code "53") (name "Net-(Q9-G)") (class "Default")
      (node (ref "Q9") (pin "1") (pinfunction "G_1") (pintype "passive"))
      (node (ref "R17") (pin "2") (pinfunction "2_2") (pintype "passive"))
      (node (ref "R21") (pin "1") (pinfunction "1_1") (pintype "passive"))
    )
    (net (code "54") (name "Net-(Q10-G)") (class "Default")
      (node (ref "Q10") (pin "1") (pinfunction "G_1") (pintype "passive"))
      (node (ref "Q8") (pin "1") (pinfunction "G_1") (pintype "passive"))
      (node (ref "Q9") (pin "3") (pinfunction "D_3") (pintype "passive"))
      (node (ref "R19") (pin "1") (pinfunction "1_1") (pintype "passive"))
    )
    (net (code "55") (name "Net-(Q10-S)") (class "Default")
      (node (ref "Q10") (pin "2") (pinfunction "S_2") (pintype "passive"))
      (node (ref "R10") (pin "2") (pinfunction "2_2") (pintype "passive"))
    )
    (net (code "56") (name "Net-(U1-CS)") (class "Default")
      (node (ref "R2") (pin "2") (pinfunction "2_2") (pintype "passive"))
      (node (ref "U1") (pin "2") (pinfunction "CS_2") (pintype "passive"))
    )
    (net (code "57") (name "Net-(U1-VCC)") (class "Default")
      (node (ref "C1") (pin "2") (pinfunction "2_2") (pintype "passive"))
      (node (ref "R1") (pin "1") (pinfunction "1_1") (pintype "passive"))
      (node (ref "U1") (pin "5") (pinfunction "VCC_5") (pintype "passive"))
    )
    (net (code "58") (name "unconnected-(J3-SBU1-PadA8)") (class "Default")
      (node (ref "J3") (pin "A8") (pinfunction "SBU1_A8") (pintype "passive"))
    )
    (net (code "59") (name "unconnected-(J3-SBU2-PadB8)") (class "Default")
      (node (ref "J3") (pin "B8") (pinfunction "SBU2_B8") (pintype "passive"))
    )
    (net (code "60") (name "unconnected-(J3-SSRXn1-PadB10)") (class "Default")
      (node (ref "J3") (pin "B10") (pinfunction "SSRXn1_B10") (pintype "passive"))
    )
    (net (code "61") (name "unconnected-(J3-SSRXn2-PadA10)") (class "Default")
      (node (ref "J3") (pin "A10") (pinfunction "SSRXn2_A10") (pintype "passive"))
    )
    (net (code "62") (name "unconnected-(J3-SSRXp1-PadB11)") (class "Default")
      (node (ref "J3") (pin "B11") (pinfunction "SSRXp1_B11") (pintype "passive"))
    )
    (net (code "63") (name "unconnected-(J3-SSRXp2-PadA11)") (class "Default")
      (node (ref "J3") (pin "A11") (pinfunction "SSRXp2_A11") (pintype "passive"))
    )
    (net (code "64") (name "unconnected-(J3-SSTXn1-PadA3)") (class "Default")
      (node (ref "J3") (pin "A3") (pinfunction "SSTXn1_A3") (pintype "passive"))
    )
    (net (code "65") (name "unconnected-(J3-SSTXn2-PadB3)") (class "Default")
      (node (ref "J3") (pin "B3") (pinfunction "SSTXn2_B3") (pintype "passive"))
    )
    (net (code "66") (name "unconnected-(J3-SSTXp1-PadA2)") (class "Default")
      (node (ref "J3") (pin "A2") (pinfunction "SSTXp1_A2") (pintype "passive"))
    )
    (net (code "67") (name "unconnected-(J3-SSTXp2-PadB2)") (class "Default")
      (node (ref "J3") (pin "B2") (pinfunction "SSTXp2_B2") (pintype "passive"))
    )
    (net (code "68") (name "unconnected-(J4-SHIELD1-Pad5)") (class "Default")
      (node (ref "J4") (pin "5") (pinfunction "SHIELD1_5") (pintype "passive"))
    )
    (net (code "69") (name "unconnected-(J4-SHIELD2-Pad6)") (class "Default")
      (node (ref "J4") (pin "6") (pinfunction "SHIELD2_6") (pintype "passive"))
    )
    (net (code "70") (name "unconnected-(Q1-D2-Pad5)") (class "Default")
      (node (ref "Q1") (pin "5") (pinfunction "D2_5") (pintype "passive"))
    )
    (net (code "71") (name "unconnected-(Q4-D1-Pad2)") (class "Default")
      (node (ref "Q4") (pin "2") (pinfunction "D1_2") (pintype "passive"))
    )
    (net (code "72") (name "unconnected-(Q5-D1-Pad2)") (class "Default")
      (node (ref "Q5") (pin "2") (pinfunction "D1_2") (pintype "passive"))
    )
    (net (code "73") (name "unconnected-(Q6-D1-Pad2)") (class "Default")
      (node (ref "Q6") (pin "2") (pinfunction "D1_2") (pintype "passive"))
    )
    (net (code "74") (name "unconnected-(Q7-D1-Pad2)") (class "Default")
      (node (ref "Q7") (pin "2") (pinfunction "D1_2") (pintype "passive"))
    )
    (net (code "75") (name "unconnected-(U1-TD-Pad4)") (class "Default")
      (node (ref "U1") (pin "4") (pinfunction "TD_4") (pintype "passive"))
    )
    (net (code "76") (name "unconnected-(U3-PA3-Pad4)") (class "Default")
      (node (ref "U3") (pin "4") (pinfunction "PA3_4") (pintype "passive"))
    )
    (net (code "77") (name "unconnected-(U3-PA7-Pad7)") (class "Default")
      (node (ref "U3") (pin "7") (pinfunction "PA7_7") (pintype "passive"))
    )
    (net (code "78") (name "unconnected-(U3-PB2-Pad6)") (class "Default")
      (node (ref "U3") (pin "6") (pinfunction "PB2_6") (pintype "passive"))
    )
  )
)
